# BT840_1_25mm_headers.net
KiCad netlist of a schematic drawn in EAGLE
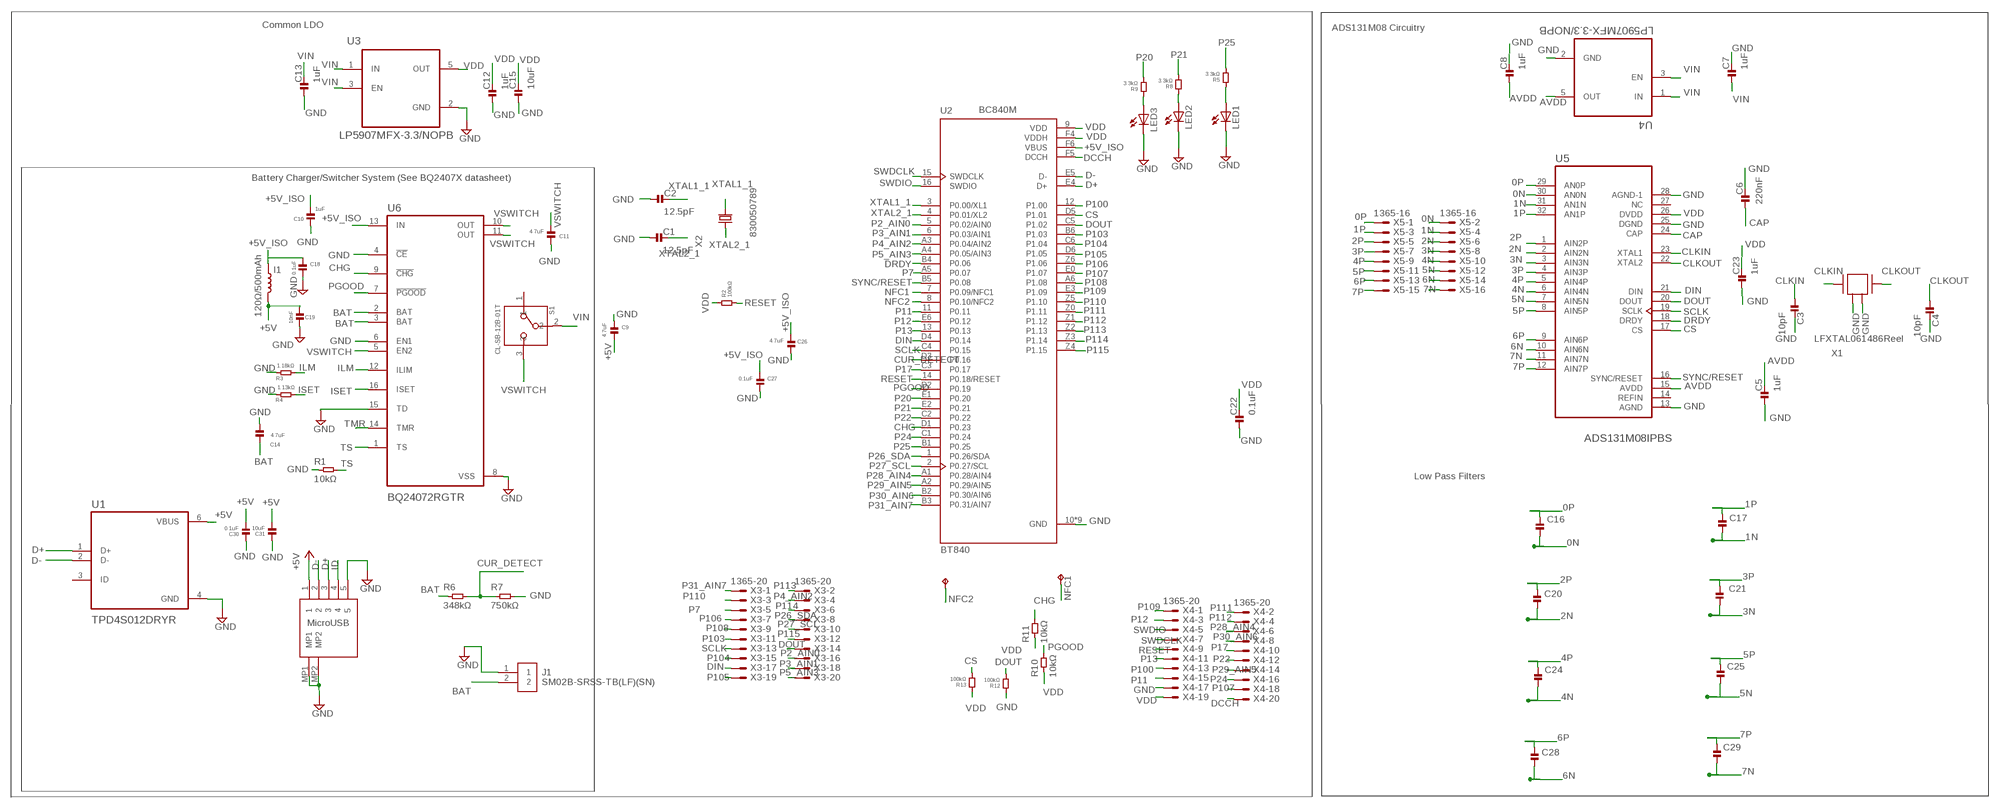
[diagram p0: schematic, sheet 1]

(export (version "E")
  (design (tool "Eeschema 10.0.6"))
  (components
    (comp (ref "C1")
      (value "12.5pF")
      (footprint "eagle-import:0201")
      (libsource (lib "eagle-import") (part "CAPACITOR.0201"))
    )
    (comp (ref "C2")
      (value "12.5pF")
      (footprint "eagle-import:0201")
      (libsource (lib "eagle-import") (part "CAPACITOR.0201"))
    )
    (comp (ref "C3")
      (value "10pF")
      (footprint "eagle-import:0201")
      (libsource (lib "eagle-import") (part "CAPACITOR.0201"))
    )
    (comp (ref "C4")
      (value "10pF")
      (footprint "eagle-import:0201")
      (libsource (lib "eagle-import") (part "CAPACITOR.0201"))
    )
    (comp (ref "C5")
      (value "1uF")
      (footprint "eagle-import:0201")
      (libsource (lib "eagle-import") (part "CAPACITOR.0201"))
    )
    (comp (ref "C6")
      (value "220nF")
      (footprint "eagle-import:0201")
      (libsource (lib "eagle-import") (part "CAPACITOR.0201"))
    )
    (comp (ref "C7")
      (value "1uF")
      (footprint "eagle-import:0201")
      (libsource (lib "eagle-import") (part "CAPACITOR.0201"))
    )
    (comp (ref "C8")
      (value "1uF")
      (footprint "eagle-import:0201")
      (libsource (lib "eagle-import") (part "CAPACITOR.0201"))
    )
    (comp (ref "C9")
      (value "4.7uF")
      (footprint "eagle-import:0201")
      (libsource (lib "eagle-import") (part "CAPACITOR.0201"))
    )
    (comp (ref "C10")
      (value "1uF")
      (footprint "eagle-import:0201")
      (libsource (lib "eagle-import") (part "CAPACITOR.0201"))
    )
    (comp (ref "C11")
      (value "4.7uF")
      (footprint "eagle-import:0201")
      (libsource (lib "eagle-import") (part "CAPACITOR.0201"))
    )
    (comp (ref "C12")
      (value "1uF")
      (footprint "eagle-import:0201")
      (libsource (lib "eagle-import") (part "CAPACITOR.0201"))
    )
    (comp (ref "C13")
      (value "1uF")
      (footprint "eagle-import:0201")
      (libsource (lib "eagle-import") (part "CAPACITOR.0201"))
    )
    (comp (ref "C14")
      (value "4.7uF")
      (footprint "eagle-import:0201")
      (libsource (lib "eagle-import") (part "CAPACITOR.0201"))
    )
    (comp (ref "C15")
      (value "10uF")
      (footprint "eagle-import:0402")
      (libsource (lib "eagle-import") (part "CAPACITOR.0402"))
    )
    (comp (ref "C16")
      (value "100pF")
      (footprint "eagle-import:0201")
      (libsource (lib "eagle-import") (part "CAPACITOR.0201"))
    )
    (comp (ref "C17")
      (value "100pF")
      (footprint "eagle-import:0201")
      (libsource (lib "eagle-import") (part "CAPACITOR.0201"))
    )
    (comp (ref "C18")
      (value "0.1uF")
      (footprint "eagle-import:0201")
      (libsource (lib "eagle-import") (part "CAPACITOR.0201"))
    )
    (comp (ref "C19")
      (value "10nF")
      (footprint "eagle-import:0201")
      (libsource (lib "eagle-import") (part "CAPACITOR.0201"))
    )
    (comp (ref "C20")
      (value "100pF")
      (footprint "eagle-import:0201")
      (libsource (lib "eagle-import") (part "CAPACITOR.0201"))
    )
    (comp (ref "C21")
      (value "100pF")
      (footprint "eagle-import:0201")
      (libsource (lib "eagle-import") (part "CAPACITOR.0201"))
    )
    (comp (ref "C22")
      (value "0.1uF")
      (footprint "eagle-import:0201")
      (libsource (lib "eagle-import") (part "CAPACITOR.0201"))
    )
    (comp (ref "C23")
      (value "1uF")
      (footprint "eagle-import:0201")
      (libsource (lib "eagle-import") (part "CAPACITOR.0201"))
    )
    (comp (ref "C24")
      (value "100pF")
      (footprint "eagle-import:0201")
      (libsource (lib "eagle-import") (part "CAPACITOR.0201"))
    )
    (comp (ref "C25")
      (value "100pF")
      (footprint "eagle-import:0201")
      (libsource (lib "eagle-import") (part "CAPACITOR.0201"))
    )
    (comp (ref "C26")
      (value "4.7uF")
      (footprint "eagle-import:0201")
      (libsource (lib "eagle-import") (part "CAPACITOR.0201"))
    )
    (comp (ref "C27")
      (value "0.1uF")
      (footprint "eagle-import:0201")
      (libsource (lib "eagle-import") (part "CAPACITOR.0201"))
    )
    (comp (ref "C28")
      (value "100pF")
      (footprint "eagle-import:0201")
      (libsource (lib "eagle-import") (part "CAPACITOR.0201"))
    )
    (comp (ref "C29")
      (value "100pF")
      (footprint "eagle-import:0201")
      (libsource (lib "eagle-import") (part "CAPACITOR.0201"))
    )
    (comp (ref "C30")
      (value "0.1uF")
      (footprint "eagle-import:0201")
      (libsource (lib "eagle-import") (part "CAPACITOR.0201"))
    )
    (comp (ref "C31")
      (value "10uF")
      (footprint "eagle-import:0402")
      (libsource (lib "eagle-import") (part "CAPACITOR.0402"))
    )
    (comp (ref "I1")
      (value "120Ω/500mAh")
      (footprint "eagle-import:0402_COILCRAFT")
      (fields (field (name "MOUSER_PART") "994-0402HP-12NXGLU"))
      (libsource (lib "eagle-import") (part "12NH-0402"))
    )
    (comp (ref "J1")
      (value "SM02B-SRSS-TB(LF)(SN)")
      (footprint "eagle-import:SM02B-SRSS-TB(LF)(SN)")
      (fields (field (name "MF") "JST Sales"))
      (libsource (lib "eagle-import") (part "SM02B-SRSS-TB(LF)(SN)"))
    )
    (comp (ref "LED1")
      (value "LEDCHIPLED_0603")
      (footprint "eagle-import:CHIPLED_0603")
      (libsource (lib "eagle-import") (part "LEDCHIPLED_0603"))
    )
    (comp (ref "LED2")
      (value "LEDCHIPLED_0603")
      (footprint "eagle-import:CHIPLED_0603")
      (libsource (lib "eagle-import") (part "LEDCHIPLED_0603"))
    )
    (comp (ref "LED3")
      (value "LEDCHIPLED_0603")
      (footprint "eagle-import:CHIPLED_0603")
      (libsource (lib "eagle-import") (part "LEDCHIPLED_0603"))
    )
    (comp (ref "NFC1")
      (value "TPTP14SQ")
      (footprint "eagle-import:TP14SQ")
      (libsource (lib "eagle-import") (part "TPTP14SQ"))
    )
    (comp (ref "NFC2")
      (value "TPTP14SQ")
      (footprint "eagle-import:TP14SQ")
      (libsource (lib "eagle-import") (part "TPTP14SQ"))
    )
    (comp (ref "R1")
      (value "10kΩ")
      (footprint "eagle-import:0201")
      (libsource (lib "eagle-import") (part "RESISTOR.0201"))
    )
    (comp (ref "R2")
      (value "100kΩ")
      (footprint "eagle-import:0201")
      (libsource (lib "eagle-import") (part "RESISTOR.0201"))
    )
    (comp (ref "R3")
      (value "1.18kΩ")
      (footprint "eagle-import:0201")
      (fields (field (name "SPICEPREFIX") "R"))
      (libsource (lib "eagle-import") (part "RESISTOR.0201"))
    )
    (comp (ref "R4")
      (value "1.13kΩ")
      (footprint "eagle-import:0201")
      (libsource (lib "eagle-import") (part "RESISTOR.0201"))
    )
    (comp (ref "R5")
      (value "3.3kΩ")
      (footprint "eagle-import:0201")
      (libsource (lib "eagle-import") (part "RESISTOR.0201"))
    )
    (comp (ref "R6")
      (value "348kΩ")
      (footprint "eagle-import:0201")
      (libsource (lib "eagle-import") (part "RESISTOR.0201"))
    )
    (comp (ref "R7")
      (value "750kΩ")
      (footprint "eagle-import:0201")
      (libsource (lib "eagle-import") (part "RESISTOR.0201"))
    )
    (comp (ref "R8")
      (value "3.3kΩ")
      (footprint "eagle-import:0201")
      (libsource (lib "eagle-import") (part "RESISTOR.0201"))
    )
    (comp (ref "R9")
      (value "3.3kΩ")
      (footprint "eagle-import:0201")
      (libsource (lib "eagle-import") (part "RESISTOR.0201"))
    )
    (comp (ref "R10")
      (value "10kΩ")
      (footprint "eagle-import:0402")
      (libsource (lib "eagle-import") (part "RESISTOR.0402"))
    )
    (comp (ref "R11")
      (value "10kΩ")
      (footprint "eagle-import:0402")
      (libsource (lib "eagle-import") (part "RESISTOR.0402"))
    )
    (comp (ref "R12")
      (value "100kΩ")
      (footprint "eagle-import:0402")
      (libsource (lib "eagle-import") (part "RESISTOR.0402"))
    )
    (comp (ref "R13")
      (value "100kΩ")
      (footprint "eagle-import:0402")
      (libsource (lib "eagle-import") (part "RESISTOR.0402"))
    )
    (comp (ref "S1")
      (value "CL-SB-12B-01T")
      (footprint "eagle-import:CL-SB-12B")
      (fields (field (name "MF") "Nidec Copal"))
      (libsource (lib "eagle-import") (part "CL-SB-12B-01T"))
    )
    (comp (ref "U1")
      (value "TPD4S012DRYR")
      (footprint "eagle-import:PSON50P145X100X60-6N")
      (fields (field (name "MF") "Texas Instruments"))
      (libsource (lib "eagle-import") (part "TPD4S012DRYR"))
    )
    (comp (ref "U2")
      (value "BT840")
      (footprint "eagle-import:XCVR_BT840")
      (fields (field (name "MF") "Fanstel Corp."))
      (libsource (lib "eagle-import") (part "BT840"))
    )
    (comp (ref "U3")
      (value "LP5907MFX-3.3/NOPB")
      (footprint "eagle-import:SOT95P280X145-5N")
      (fields (field (name "MF") "Texas Instruments"))
      (libsource (lib "eagle-import") (part "LP5907MFX-3.3/NOPB"))
    )
    (comp (ref "U4")
      (value "LP5907MFX-3.3/NOPB")
      (footprint "eagle-import:SOT95P280X145-5N")
      (fields (field (name "MF") "Texas Instruments"))
      (libsource (lib "eagle-import") (part "LP5907MFX-3.3/NOPB"))
    )
    (comp (ref "U5")
      (value "ADS131M08IPBS")
      (footprint "eagle-import:QFP50P700X700X120-32N")
      (fields (field (name "MF") "Texas Instruments"))
      (libsource (lib "eagle-import") (part "ADS131M08IPBS"))
    )
    (comp (ref "U6")
      (value "BQ24072RGTR")
      (footprint "eagle-import:QFN50P300X300X100-17N")
      (fields (field (name "MF") "Texas Instruments"))
      (libsource (lib "eagle-import") (part "BQ24072RGTR"))
    )
    (comp (ref "U7")
      (value "DX4R005JJ2R1800")
      (footprint "eagle-import:DX4R005JJ2R1800")
      (fields (field (name "MF") "JAE Electronics"))
      (libsource (lib "eagle-import") (part "DX4R005JJ2R1800"))
    )
    (comp (ref "X1")
      (value "ABM3B-8.000MHZ-B2-T")
      (footprint "eagle-import:ABM3B-8.000MHZ-B2-T")
      (fields
        (field (name "DIGIKEY_PART_NUMBER") "535-9720-2-ND")
        (field (name "MANUFACTURER") "Abracon LLC")
        (field (name "CREATED_BY") "PCBLayout.com")
      )
      (libsource (lib "eagle-import") (part "ABM3B-8.000MHZ-B2-T"))
    )
    (comp (ref "X2")
      (value "FC-12M")
      (footprint "eagle-import:FC-12M")
      (libsource (lib "eagle-import") (part "FC-12M"))
    )
    (comp (ref "X3")
      (value "1365-20")
      (footprint "eagle-import:1365-20")
      (libsource (lib "eagle-import") (part "1365-20"))
    )
    (comp (ref "X4")
      (value "1365-20")
      (footprint "eagle-import:1365-20")
      (libsource (lib "eagle-import") (part "1365-20"))
    )
    (comp (ref "X5")
      (value "1365-16")
      (footprint "eagle-import:1365-16")
      (libsource (lib "eagle-import") (part "1365-16"))
    )
  )
  (nets
    (net (code "1") (name "+5V") (class "Default")
      (node (ref "C19") (pin "2") (pinfunction "2_2") (pintype "bidirectional"))
      (node (ref "C30") (pin "2") (pinfunction "2_2") (pintype "bidirectional"))
      (node (ref "C31") (pin "2") (pinfunction "2_2") (pintype "bidirectional"))
      (node (ref "C9") (pin "2") (pinfunction "2_2") (pintype "bidirectional"))
      (node (ref "I1") (pin "P$2") (pinfunction "2_P$2") (pintype "passive"))
      (node (ref "U1") (pin "6") (pinfunction "VBUS_6") (pintype "power_in"))
      (node (ref "U7") (pin "1") (pinfunction "1_1") (pintype "bidirectional"))
    )
    (net (code "2") (name "+5V_ISO") (class "Default")
      (node (ref "C10") (pin "2") (pinfunction "2_2") (pintype "bidirectional"))
      (node (ref "C18") (pin "1") (pinfunction "1_1") (pintype "bidirectional"))
      (node (ref "C26") (pin "2") (pinfunction "2_2") (pintype "bidirectional"))
      (node (ref "C27") (pin "2") (pinfunction "2_2") (pintype "bidirectional"))
      (node (ref "I1") (pin "P$1") (pinfunction "1_P$1") (pintype "passive"))
      (node (ref "U2") (pin "F6") (pinfunction "VBUS_F6") (pintype "power_in"))
      (node (ref "U6") (pin "13") (pinfunction "IN_13") (pintype "input"))
    )
    (net (code "3") (name "0N") (class "Default")
      (node (ref "C16") (pin "2") (pinfunction "2_2") (pintype "bidirectional"))
      (node (ref "U5") (pin "30") (pinfunction "AN0N_30") (pintype "bidirectional"))
      (node (ref "X5") (pin "2") (pinfunction "S_2") (pintype "passive"))
    )
    (net (code "4") (name "0P") (class "Default")
      (node (ref "C16") (pin "1") (pinfunction "1_1") (pintype "bidirectional"))
      (node (ref "U5") (pin "29") (pinfunction "AN0P_29") (pintype "bidirectional"))
      (node (ref "X5") (pin "1") (pinfunction "S_1") (pintype "passive"))
    )
    (net (code "5") (name "1N") (class "Default")
      (node (ref "C17") (pin "2") (pinfunction "2_2") (pintype "bidirectional"))
      (node (ref "U5") (pin "31") (pinfunction "AN1N_31") (pintype "bidirectional"))
      (node (ref "X5") (pin "4") (pinfunction "S_4") (pintype "passive"))
    )
    (net (code "6") (name "1P") (class "Default")
      (node (ref "C17") (pin "1") (pinfunction "1_1") (pintype "bidirectional"))
      (node (ref "U5") (pin "32") (pinfunction "AN1P_32") (pintype "bidirectional"))
      (node (ref "X5") (pin "3") (pinfunction "S_3") (pintype "passive"))
    )
    (net (code "7") (name "2N") (class "Default")
      (node (ref "C20") (pin "2") (pinfunction "2_2") (pintype "bidirectional"))
      (node (ref "U5") (pin "2") (pinfunction "AIN2N_2") (pintype "input"))
      (node (ref "X5") (pin "6") (pinfunction "S_6") (pintype "passive"))
    )
    (net (code "8") (name "2P") (class "Default")
      (node (ref "C20") (pin "1") (pinfunction "1_1") (pintype "bidirectional"))
      (node (ref "U5") (pin "1") (pinfunction "AIN2P_1") (pintype "input"))
      (node (ref "X5") (pin "5") (pinfunction "S_5") (pintype "passive"))
    )
    (net (code "9") (name "3N") (class "Default")
      (node (ref "C21") (pin "2") (pinfunction "2_2") (pintype "bidirectional"))
      (node (ref "U5") (pin "3") (pinfunction "AIN3N_3") (pintype "input"))
      (node (ref "X5") (pin "8") (pinfunction "S_8") (pintype "passive"))
    )
    (net (code "10") (name "3P") (class "Default")
      (node (ref "C21") (pin "1") (pinfunction "1_1") (pintype "bidirectional"))
      (node (ref "U5") (pin "4") (pinfunction "AIN3P_4") (pintype "input"))
      (node (ref "X5") (pin "7") (pinfunction "S_7") (pintype "passive"))
    )
    (net (code "11") (name "4N") (class "Default")
      (node (ref "C24") (pin "2") (pinfunction "2_2") (pintype "bidirectional"))
      (node (ref "U5") (pin "6") (pinfunction "AIN4N_6") (pintype "input"))
      (node (ref "X5") (pin "10") (pinfunction "S_10") (pintype "passive"))
    )
    (net (code "12") (name "4P") (class "Default")
      (node (ref "C24") (pin "1") (pinfunction "1_1") (pintype "bidirectional"))
      (node (ref "U5") (pin "5") (pinfunction "AIN4P_5") (pintype "input"))
      (node (ref "X5") (pin "9") (pinfunction "S_9") (pintype "passive"))
    )
    (net (code "13") (name "5N") (class "Default")
      (node (ref "C25") (pin "2") (pinfunction "2_2") (pintype "bidirectional"))
      (node (ref "U5") (pin "7") (pinfunction "AIN5N_7") (pintype "input"))
      (node (ref "X5") (pin "12") (pinfunction "S_12") (pintype "passive"))
    )
    (net (code "14") (name "5P") (class "Default")
      (node (ref "C25") (pin "1") (pinfunction "1_1") (pintype "bidirectional"))
      (node (ref "U5") (pin "8") (pinfunction "AIN5P_8") (pintype "input"))
      (node (ref "X5") (pin "11") (pinfunction "S_11") (pintype "passive"))
    )
    (net (code "15") (name "6N") (class "Default")
      (node (ref "C28") (pin "2") (pinfunction "2_2") (pintype "bidirectional"))
      (node (ref "U5") (pin "10") (pinfunction "AIN6N_10") (pintype "input"))
      (node (ref "X5") (pin "14") (pinfunction "S_14") (pintype "passive"))
    )
    (net (code "16") (name "6P") (class "Default")
      (node (ref "C28") (pin "1") (pinfunction "1_1") (pintype "bidirectional"))
      (node (ref "U5") (pin "9") (pinfunction "AIN6P_9") (pintype "input"))
      (node (ref "X5") (pin "13") (pinfunction "S_13") (pintype "passive"))
    )
    (net (code "17") (name "7N") (class "Default")
      (node (ref "C29") (pin "2") (pinfunction "2_2") (pintype "bidirectional"))
      (node (ref "U5") (pin "11") (pinfunction "AIN7N_11") (pintype "input"))
      (node (ref "X5") (pin "16") (pinfunction "S_16") (pintype "passive"))
    )
    (net (code "18") (name "7P") (class "Default")
      (node (ref "C29") (pin "1") (pinfunction "1_1") (pintype "bidirectional"))
      (node (ref "U5") (pin "12") (pinfunction "AIN7P_12") (pintype "input"))
      (node (ref "X5") (pin "15") (pinfunction "S_15") (pintype "passive"))
    )
    (net (code "19") (name "AVDD") (class "Default")
      (node (ref "C5") (pin "2") (pinfunction "2_2") (pintype "bidirectional"))
      (node (ref "C8") (pin "1") (pinfunction "1_1") (pintype "bidirectional"))
      (node (ref "U4") (pin "5") (pinfunction "OUT_5") (pintype "output"))
      (node (ref "U5") (pin "15") (pinfunction "AVDD_15") (pintype "power_in"))
    )
    (net (code "20") (name "BAT") (class "Default")
      (node (ref "C14") (pin "2") (pinfunction "2_2") (pintype "bidirectional"))
      (node (ref "J1") (pin "2") (pinfunction "2_2") (pintype "bidirectional"))
      (node (ref "R6") (pin "1") (pinfunction "1_1") (pintype "bidirectional"))
      (node (ref "U6") (pin "2") (pinfunction "BAT_2") (pintype "bidirectional"))
      (node (ref "U6") (pin "3") (pinfunction "BAT_3") (pintype "bidirectional"))
    )
    (net (code "21") (name "CAP") (class "Default")
      (node (ref "C6") (pin "1") (pinfunction "1_1") (pintype "bidirectional"))
      (node (ref "U5") (pin "24") (pinfunction "CAP_24") (pintype "bidirectional"))
    )
    (net (code "22") (name "CHG") (class "Default")
      (node (ref "R11") (pin "2") (pinfunction "2_2") (pintype "bidirectional"))
      (node (ref "U2") (pin "D1") (pinfunction "P0.23_D1") (pintype "bidirectional"))
      (node (ref "U6") (pin "9") (pinfunction "~{CHG}_9") (pintype "bidirectional"))
    )
    (net (code "23") (name "CLKIN") (class "Default")
      (node (ref "C3") (pin "1") (pinfunction "1_1") (pintype "bidirectional"))
      (node (ref "U5") (pin "23") (pinfunction "XTAL1_23") (pintype "bidirectional"))
      (node (ref "X1") (pin "1") (pinfunction "1_1") (pintype "passive"))
    )
    (net (code "24") (name "CLKOUT") (class "Default")
      (node (ref "C4") (pin "1") (pinfunction "1_1") (pintype "bidirectional"))
      (node (ref "U5") (pin "22") (pinfunction "XTAL2_22") (pintype "bidirectional"))
      (node (ref "X1") (pin "3") (pinfunction "3_3") (pintype "passive"))
    )
    (net (code "25") (name "CS") (class "Default")
      (node (ref "R13") (pin "1") (pinfunction "1_1") (pintype "bidirectional"))
      (node (ref "U2") (pin "D5") (pinfunction "P1.01_D5") (pintype "bidirectional"))
      (node (ref "U5") (pin "17") (pinfunction "CS_17") (pintype "bidirectional"))
    )
    (net (code "26") (name "CUR_DETECT") (class "Default")
      (node (ref "R6") (pin "2") (pinfunction "2_2") (pintype "bidirectional"))
      (node (ref "R7") (pin "1") (pinfunction "1_1") (pintype "bidirectional"))
      (node (ref "U2") (pin "D3") (pinfunction "P0.16_D3") (pintype "bidirectional"))
    )
    (net (code "27") (name "D+") (class "Default")
      (node (ref "U1") (pin "1") (pinfunction "D+_1") (pintype "bidirectional"))
      (node (ref "U2") (pin "E4") (pinfunction "D+_E4") (pintype "bidirectional"))
      (node (ref "U7") (pin "3") (pinfunction "3_3") (pintype "bidirectional"))
    )
    (net (code "28") (name "D-") (class "Default")
      (node (ref "U1") (pin "2") (pinfunction "D-_2") (pintype "bidirectional"))
      (node (ref "U2") (pin "E5") (pinfunction "D-_E5") (pintype "bidirectional"))
      (node (ref "U7") (pin "2") (pinfunction "2_2") (pintype "bidirectional"))
    )
    (net (code "29") (name "DCCH") (class "Default")
      (node (ref "U2") (pin "F5") (pinfunction "DCCH_F5") (pintype "power_in"))
      (node (ref "X4") (pin "20") (pinfunction "S_20") (pintype "passive"))
    )
    (net (code "30") (name "DIN") (class "Default")
      (node (ref "U2") (pin "D4") (pinfunction "P0.14_D4") (pintype "bidirectional"))
      (node (ref "U5") (pin "21") (pinfunction "DIN_21") (pintype "input"))
      (node (ref "X3") (pin "17") (pinfunction "S_17") (pintype "passive"))
    )
    (net (code "31") (name "DOUT") (class "Default")
      (node (ref "R12") (pin "1") (pinfunction "1_1") (pintype "bidirectional"))
      (node (ref "U2") (pin "C5") (pinfunction "P1.02_C5") (pintype "bidirectional"))
      (node (ref "U5") (pin "20") (pinfunction "DOUT_20") (pintype "output"))
      (node (ref "X3") (pin "14") (pinfunction "S_14") (pintype "passive"))
    )
    (net (code "32") (name "DRDY") (class "Default")
      (node (ref "U2") (pin "B4") (pinfunction "P0.06_B4") (pintype "bidirectional"))
      (node (ref "U5") (pin "18") (pinfunction "DRDY_18") (pintype "output"))
    )
    (net (code "33") (name "GND") (class "Default")
      (node (ref "C1") (pin "1") (pinfunction "1_1") (pintype "bidirectional"))
      (node (ref "C10") (pin "1") (pinfunction "1_1") (pintype "bidirectional"))
      (node (ref "C11") (pin "1") (pinfunction "1_1") (pintype "bidirectional"))
      (node (ref "C12") (pin "1") (pinfunction "1_1") (pintype "bidirectional"))
      (node (ref "C13") (pin "1") (pinfunction "1_1") (pintype "bidirectional"))
      (node (ref "C14") (pin "1") (pinfunction "1_1") (pintype "bidirectional"))
      (node (ref "C15") (pin "1") (pinfunction "1_1") (pintype "bidirectional"))
      (node (ref "C18") (pin "2") (pinfunction "2_2") (pintype "bidirectional"))
      (node (ref "C19") (pin "1") (pinfunction "1_1") (pintype "bidirectional"))
      (node (ref "C2") (pin "1") (pinfunction "1_1") (pintype "bidirectional"))
      (node (ref "C22") (pin "1") (pinfunction "1_1") (pintype "bidirectional"))
      (node (ref "C23") (pin "1") (pinfunction "1_1") (pintype "bidirectional"))
      (node (ref "C26") (pin "1") (pinfunction "1_1") (pintype "bidirectional"))
      (node (ref "C27") (pin "1") (pinfunction "1_1") (pintype "bidirectional"))
      (node (ref "C3") (pin "2") (pinfunction "2_2") (pintype "bidirectional"))
      (node (ref "C30") (pin "1") (pinfunction "1_1") (pintype "bidirectional"))
      (node (ref "C31") (pin "1") (pinfunction "1_1") (pintype "bidirectional"))
      (node (ref "C4") (pin "2") (pinfunction "2_2") (pintype "bidirectional"))
      (node (ref "C5") (pin "1") (pinfunction "1_1") (pintype "bidirectional"))
      (node (ref "C6") (pin "2") (pinfunction "2_2") (pintype "bidirectional"))
      (node (ref "C7") (pin "2") (pinfunction "2_2") (pintype "bidirectional"))
      (node (ref "C8") (pin "2") (pinfunction "2_2") (pintype "bidirectional"))
      (node (ref "C9") (pin "1") (pinfunction "1_1") (pintype "bidirectional"))
      (node (ref "J1") (pin "1") (pinfunction "1_1") (pintype "bidirectional"))
      (node (ref "LED1") (pin "C") (pinfunction "C_C") (pintype "passive"))
      (node (ref "LED2") (pin "C") (pinfunction "C_C") (pintype "passive"))
      (node (ref "LED3") (pin "C") (pinfunction "C_C") (pintype "passive"))
      (node (ref "R1") (pin "1") (pinfunction "1_1") (pintype "bidirectional"))
      (node (ref "R12") (pin "2") (pinfunction "2_2") (pintype "bidirectional"))
      (node (ref "R3") (pin "1") (pinfunction "1_1") (pintype "bidirectional"))
      (node (ref "R4") (pin "1") (pinfunction "1_1") (pintype "bidirectional"))
      (node (ref "R7") (pin "2") (pinfunction "2_2") (pintype "bidirectional"))
      (node (ref "U1") (pin "4") (pinfunction "GND_4") (pintype "power_in"))
      (node (ref "U2") (pin "10") (pinfunction "GND_10") (pintype "power_in"))
      (node (ref "U2") (pin "A0") (pinfunction "GND_A0") (pintype "power_in"))
      (node (ref "U2") (pin "B0") (pinfunction "GND_B0") (pintype "power_in"))
      (node (ref "U2") (pin "C0") (pinfunction "GND_C0") (pintype "power_in"))
      (node (ref "U2") (pin "D0") (pinfunction "GND_D0") (pintype "power_in"))
      (node (ref "U2") (pin "F0") (pinfunction "GND_F0") (pintype "power_in"))
      (node (ref "U2") (pin "F1") (pinfunction "GND_F1") (pintype "power_in"))
      (node (ref "U2") (pin "F2") (pinfunction "GND_F2") (pintype "power_in"))
      (node (ref "U2") (pin "F3") (pinfunction "GND_F3") (pintype "power_in"))
      (node (ref "U3") (pin "2") (pinfunction "GND_2") (pintype "power_in"))
      (node (ref "U4") (pin "2") (pinfunction "GND_2") (pintype "power_in"))
      (node (ref "U5") (pin "13") (pinfunction "AGND_13") (pintype "power_in"))
      (node (ref "U5") (pin "25") (pinfunction "DGND_25") (pintype "power_in"))
      (node (ref "U5") (pin "28") (pinfunction "AGND-1_28") (pintype "power_in"))
      (node (ref "U6") (pin "15") (pinfunction "TD_15") (pintype "bidirectional"))
      (node (ref "U6") (pin "4") (pinfunction "~{CE}_4") (pintype "bidirectional"))
      (node (ref "U6") (pin "6") (pinfunction "EN1_6") (pintype "bidirectional"))
      (node (ref "U6") (pin "8") (pinfunction "VSS_8") (pintype "power_in"))
      (node (ref "U7") (pin "5") (pinfunction "5_5") (pintype "bidirectional"))
      (node (ref "U7") (pin "MP1") (pinfunction "MP1_MP1") (pintype "bidirectional"))
      (node (ref "U7") (pin "MP2") (pinfunction "MP2_MP2") (pintype "bidirectional"))
      (node (ref "X1") (pin "2") (pinfunction "2_2") (pintype "passive"))
      (node (ref "X1") (pin "4") (pinfunction "4_4") (pintype "passive"))
      (node (ref "X4") (pin "17") (pinfunction "S_17") (pintype "passive"))
    )
    (net (code "34") (name "ID") (class "Default")
      (node (ref "U7") (pin "4") (pinfunction "4_4") (pintype "bidirectional"))
    )
    (net (code "35") (name "ILM") (class "Default")
      (node (ref "R3") (pin "2") (pinfunction "2_2") (pintype "bidirectional"))
      (node (ref "U6") (pin "12") (pinfunction "ILIM_12") (pintype "bidirectional"))
    )
    (net (code "36") (name "ISET") (class "Default")
      (node (ref "R4") (pin "2") (pinfunction "2_2") (pintype "bidirectional"))
      (node (ref "U6") (pin "16") (pinfunction "ISET_16") (pintype "bidirectional"))
    )
    (net (code "37") (name "NFC1") (class "Default")
      (node (ref "NFC2") (pin "TP") (pinfunction "TP_TP") (pintype "input"))
      (node (ref "U2") (pin "7") (pinfunction "P0.09/NFC1_7") (pintype "bidirectional"))
    )
    (net (code "38") (name "NFC2") (class "Default")
      (node (ref "NFC1") (pin "TP") (pinfunction "TP_TP") (pintype "input"))
      (node (ref "U2") (pin "8") (pinfunction "P0.10/NFC2_8") (pintype "bidirectional"))
    )
    (net (code "39") (name "Net-(LED1-PadA)") (class "Default")
      (node (ref "LED1") (pin "A") (pinfunction "A_A") (pintype "passive"))
      (node (ref "R5") (pin "2") (pinfunction "2_2") (pintype "bidirectional"))
    )
    (net (code "40") (name "Net-(LED2-PadA)") (class "Default")
      (node (ref "LED2") (pin "A") (pinfunction "A_A") (pintype "passive"))
      (node (ref "R8") (pin "2") (pinfunction "2_2") (pintype "bidirectional"))
    )
    (net (code "41") (name "Net-(LED3-PadA)") (class "Default")
      (node (ref "LED3") (pin "A") (pinfunction "A_A") (pintype "passive"))
      (node (ref "R9") (pin "2") (pinfunction "2_2") (pintype "bidirectional"))
    )
    (net (code "42") (name "P2_AIN0") (class "Default")
      (node (ref "U2") (pin "5") (pinfunction "P0.02/AIN0_5") (pintype "bidirectional"))
      (node (ref "X3") (pin "16") (pinfunction "S_16") (pintype "passive"))
    )
    (net (code "43") (name "P3_AIN1") (class "Default")
      (node (ref "U2") (pin "6") (pinfunction "P0.03/AIN1_6") (pintype "bidirectional"))
      (node (ref "X3") (pin "18") (pinfunction "S_18") (pintype "passive"))
    )
    (net (code "44") (name "P4_AIN2") (class "Default")
      (node (ref "U2") (pin "A3") (pinfunction "P0.04/AIN2_A3") (pintype "bidirectional"))
      (node (ref "X3") (pin "4") (pinfunction "S_4") (pintype "passive"))
    )
    (net (code "45") (name "P5_AIN3") (class "Default")
      (node (ref "U2") (pin "A4") (pinfunction "P0.05/AIN3_A4") (pintype "bidirectional"))
      (node (ref "X3") (pin "20") (pinfunction "S_20") (pintype "passive"))
    )
    (net (code "46") (name "P7") (class "Default")
      (node (ref "U2") (pin "A5") (pinfunction "P0.07_A5") (pintype "bidirectional"))
      (node (ref "X3") (pin "5") (pinfunction "S_5") (pintype "passive"))
    )
    (net (code "47") (name "P11") (class "Default")
      (node (ref "U2") (pin "11") (pinfunction "P0.11_11") (pintype "bidirectional"))
      (node (ref "X4") (pin "15") (pinfunction "S_15") (pintype "passive"))
    )
    (net (code "48") (name "P12") (class "Default")
      (node (ref "U2") (pin "E6") (pinfunction "P0.12_E6") (pintype "bidirectional"))
      (node (ref "X4") (pin "3") (pinfunction "S_3") (pintype "passive"))
    )
    (net (code "49") (name "P13") (class "Default")
      (node (ref "U2") (pin "13") (pinfunction "P0.13_13") (pintype "bidirectional"))
      (node (ref "X4") (pin "11") (pinfunction "S_11") (pintype "passive"))
    )
    (net (code "50") (name "P17") (class "Default")
      (node (ref "U2") (pin "C3") (pinfunction "P0.17_C3") (pintype "bidirectional"))
      (node (ref "X4") (pin "10") (pinfunction "S_10") (pintype "passive"))
    )
    (net (code "51") (name "P20") (class "Default")
      (node (ref "R9") (pin "1") (pinfunction "1_1") (pintype "bidirectional"))
      (node (ref "U2") (pin "E1") (pinfunction "P0.20_E1") (pintype "bidirectional"))
    )
    (net (code "52") (name "P21") (class "Default")
      (node (ref "R8") (pin "1") (pinfunction "1_1") (pintype "bidirectional"))
      (node (ref "U2") (pin "E2") (pinfunction "P0.21_E2") (pintype "bidirectional"))
    )
    (net (code "53") (name "P22") (class "Default")
      (node (ref "U2") (pin "C2") (pinfunction "P0.22_C2") (pintype "bidirectional"))
      (node (ref "X4") (pin "12") (pinfunction "S_12") (pintype "passive"))
    )
    (net (code "54") (name "P24") (class "Default")
      (node (ref "U2") (pin "C1") (pinfunction "P0.24_C1") (pintype "bidirectional"))
      (node (ref "X4") (pin "16") (pinfunction "S_16") (pintype "passive"))
    )
    (net (code "55") (name "P25") (class "Default")
      (node (ref "R5") (pin "1") (pinfunction "1_1") (pintype "bidirectional"))
      (node (ref "U2") (pin "B1") (pinfunction "P0.25_B1") (pintype "bidirectional"))
    )
    (net (code "56") (name "P26_SDA") (class "Default")
      (node (ref "U2") (pin "1") (pinfunction "P0.26/SDA_1") (pintype "bidirectional"))
      (node (ref "X3") (pin "8") (pinfunction "S_8") (pintype "passive"))
    )
    (net (code "57") (name "P27_SCL") (class "Default")
      (node (ref "U2") (pin "2") (pinfunction "P0.27/SCL_2") (pintype "bidirectional"))
      (node (ref "X3") (pin "10") (pinfunction "S_10") (pintype "passive"))
    )
    (net (code "58") (name "P28_AIN4") (class "Default")
      (node (ref "U2") (pin "A1") (pinfunction "P0.28/AIN4_A1") (pintype "bidirectional"))
      (node (ref "X4") (pin "6") (pinfunction "S_6") (pintype "passive"))
    )
    (net (code "59") (name "P29_AIN5") (class "Default")
      (node (ref "U2") (pin "A2") (pinfunction "P0.29/AIN5_A2") (pintype "bidirectional"))
      (node (ref "X4") (pin "14") (pinfunction "S_14") (pintype "passive"))
    )
    (net (code "60") (name "P30_AIN6") (class "Default")
      (node (ref "U2") (pin "B2") (pinfunction "P0.30/AIN6_B2") (pintype "bidirectional"))
      (node (ref "X4") (pin "8") (pinfunction "S_8") (pintype "passive"))
    )
    (net (code "61") (name "P31_AIN7") (class "Default")
      (node (ref "U2") (pin "B3") (pinfunction "P0.31/AIN7_B3") (pintype "bidirectional"))
      (node (ref "X3") (pin "1") (pinfunction "S_1") (pintype "passive"))
    )
    (net (code "62") (name "P100") (class "Default")
      (node (ref "U2") (pin "12") (pinfunction "P1.00_12") (pintype "bidirectional"))
      (node (ref "X4") (pin "13") (pinfunction "S_13") (pintype "passive"))
    )
    (net (code "63") (name "P103") (class "Default")
      (node (ref "U2") (pin "B6") (pinfunction "P1.03_B6") (pintype "bidirectional"))
      (node (ref "X3") (pin "11") (pinfunction "S_11") (pintype "passive"))
    )
    (net (code "64") (name "P104") (class "Default")
      (node (ref "U2") (pin "C6") (pinfunction "P1.04_C6") (pintype "bidirectional"))
      (node (ref "X3") (pin "15") (pinfunction "S_15") (pintype "passive"))
    )
    (net (code "65") (name "P105") (class "Default")
      (node (ref "U2") (pin "D6") (pinfunction "P1.05_D6") (pintype "bidirectional"))
      (node (ref "X3") (pin "19") (pinfunction "S_19") (pintype "passive"))
    )
    (net (code "66") (name "P106") (class "Default")
      (node (ref "U2") (pin "Z6") (pinfunction "P1.06_Z6") (pintype "bidirectional"))
      (node (ref "X3") (pin "7") (pinfunction "S_7") (pintype "passive"))
    )
    (net (code "67") (name "P107") (class "Default")
      (node (ref "U2") (pin "E0") (pinfunction "P1.07_E0") (pintype "bidirectional"))
      (node (ref "X4") (pin "18") (pinfunction "S_18") (pintype "passive"))
    )
    (net (code "68") (name "P108") (class "Default")
      (node (ref "U2") (pin "A6") (pinfunction "P1.08_A6") (pintype "bidirectional"))
      (node (ref "X3") (pin "9") (pinfunction "S_9") (pintype "passive"))
    )
    (net (code "69") (name "P109") (class "Default")
      (node (ref "U2") (pin "E3") (pinfunction "P1.09_E3") (pintype "bidirectional"))
      (node (ref "X4") (pin "1") (pinfunction "S_1") (pintype "passive"))
    )
    (net (code "70") (name "P110") (class "Default")
      (node (ref "U2") (pin "Z5") (pinfunction "P1.10_Z5") (pintype "bidirectional"))
      (node (ref "X3") (pin "3") (pinfunction "S_3") (pintype "passive"))
    )
    (net (code "71") (name "P111") (class "Default")
      (node (ref "U2") (pin "Z0") (pinfunction "P1.11_Z0") (pintype "bidirectional"))
      (node (ref "X4") (pin "2") (pinfunction "S_2") (pintype "passive"))
    )
    (net (code "72") (name "P112") (class "Default")
      (node (ref "U2") (pin "Z1") (pinfunction "P1.12_Z1") (pintype "bidirectional"))
      (node (ref "X4") (pin "4") (pinfunction "S_4") (pintype "passive"))
    )
    (net (code "73") (name "P113") (class "Default")
      (node (ref "U2") (pin "Z2") (pinfunction "P1.13_Z2") (pintype "bidirectional"))
      (node (ref "X3") (pin "2") (pinfunction "S_2") (pintype "passive"))
    )
    (net (code "74") (name "P114") (class "Default")
      (node (ref "U2") (pin "Z3") (pinfunction "P1.14_Z3") (pintype "bidirectional"))
      (node (ref "X3") (pin "6") (pinfunction "S_6") (pintype "passive"))
    )
    (net (code "75") (name "P115") (class "Default")
      (node (ref "U2") (pin "Z4") (pinfunction "P1.15_Z4") (pintype "bidirectional"))
      (node (ref "X3") (pin "12") (pinfunction "S_12") (pintype "passive"))
    )
    (net (code "76") (name "PGOOD") (class "Default")
      (node (ref "R10") (pin "2") (pinfunction "2_2") (pintype "bidirectional"))
      (node (ref "U2") (pin "D2") (pinfunction "P0.19_D2") (pintype "bidirectional"))
      (node (ref "U6") (pin "7") (pinfunction "~{PGOOD}_7") (pintype "bidirectional"))
    )
    (net (code "77") (name "RESET") (class "Default")
      (node (ref "R2") (pin "1") (pinfunction "1_1") (pintype "bidirectional"))
      (node (ref "U2") (pin "14") (pinfunction "P0.18/RESET_14") (pintype "bidirectional"))
      (node (ref "X4") (pin "9") (pinfunction "S_9") (pintype "passive"))
    )
    (net (code "78") (name "SCLK") (class "Default")
      (node (ref "U2") (pin "C4") (pinfunction "P0.15_C4") (pintype "bidirectional"))
      (node (ref "U5") (pin "19") (pinfunction "SCLK_19") (pintype "input"))
      (node (ref "X3") (pin "13") (pinfunction "S_13") (pintype "passive"))
    )
    (net (code "79") (name "SWDCLK") (class "Default")
      (node (ref "U2") (pin "15") (pinfunction "SWDCLK_15") (pintype "input"))
      (node (ref "X4") (pin "7") (pinfunction "S_7") (pintype "passive"))
    )
    (net (code "80") (name "SWDIO") (class "Default")
      (node (ref "U2") (pin "16") (pinfunction "SWDIO_16") (pintype "bidirectional"))
      (node (ref "X4") (pin "5") (pinfunction "S_5") (pintype "passive"))
    )
    (net (code "81") (name "SYNC{slash}RESET") (class "Default")
      (node (ref "U2") (pin "B5") (pinfunction "P0.08_B5") (pintype "bidirectional"))
      (node (ref "U5") (pin "16") (pinfunction "SYNC/RESET_16") (pintype "bidirectional"))
    )
    (net (code "82") (name "TMR") (class "Default")
      (node (ref "U6") (pin "14") (pinfunction "TMR_14") (pintype "bidirectional"))
    )
    (net (code "83") (name "TS") (class "Default")
      (node (ref "R1") (pin "2") (pinfunction "2_2") (pintype "bidirectional"))
      (node (ref "U6") (pin "1") (pinfunction "TS_1") (pintype "bidirectional"))
    )
    (net (code "84") (name "VDD") (class "Default")
      (node (ref "C12") (pin "2") (pinfunction "2_2") (pintype "bidirectional"))
      (node (ref "C15") (pin "2") (pinfunction "2_2") (pintype "bidirectional"))
      (node (ref "C22") (pin "2") (pinfunction "2_2") (pintype "bidirectional"))
      (node (ref "C23") (pin "2") (pinfunction "2_2") (pintype "bidirectional"))
      (node (ref "R10") (pin "1") (pinfunction "1_1") (pintype "bidirectional"))
      (node (ref "R11") (pin "1") (pinfunction "1_1") (pintype "bidirectional"))
      (node (ref "R13") (pin "2") (pinfunction "2_2") (pintype "bidirectional"))
      (node (ref "R2") (pin "2") (pinfunction "2_2") (pintype "bidirectional"))
      (node (ref "U2") (pin "9") (pinfunction "VDD_9") (pintype "power_in"))
      (node (ref "U2") (pin "F4") (pinfunction "VDDH_F4") (pintype "power_in"))
      (node (ref "U3") (pin "5") (pinfunction "OUT_5") (pintype "output"))
      (node (ref "U5") (pin "26") (pinfunction "DVDD_26") (pintype "power_in"))
      (node (ref "X4") (pin "19") (pinfunction "S_19") (pintype "passive"))
    )
    (net (code "85") (name "VIN") (class "Default")
      (node (ref "C13") (pin "2") (pinfunction "2_2") (pintype "bidirectional"))
      (node (ref "C7") (pin "1") (pinfunction "1_1") (pintype "bidirectional"))
      (node (ref "S1") (pin "2") (pinfunction "2_2") (pintype "bidirectional"))
      (node (ref "U3") (pin "1") (pinfunction "IN_1") (pintype "input"))
      (node (ref "U3") (pin "3") (pinfunction "EN_3") (pintype "input"))
      (node (ref "U4") (pin "1") (pinfunction "IN_1") (pintype "input"))
      (node (ref "U4") (pin "3") (pinfunction "EN_3") (pintype "input"))
    )
    (net (code "86") (name "VSWITCH") (class "Default")
      (node (ref "C11") (pin "2") (pinfunction "2_2") (pintype "bidirectional"))
      (node (ref "S1") (pin "3") (pinfunction "3_3") (pintype "bidirectional"))
      (node (ref "U6") (pin "10") (pinfunction "OUT_10") (pintype "output"))
      (node (ref "U6") (pin "11") (pinfunction "OUT_11") (pintype "output"))
      (node (ref "U6") (pin "5") (pinfunction "EN2_5") (pintype "bidirectional"))
    )
    (net (code "87") (name "XTAL1_1") (class "Default")
      (node (ref "C2") (pin "2") (pinfunction "2_2") (pintype "bidirectional"))
      (node (ref "U2") (pin "3") (pinfunction "P0.00/XL1_3") (pintype "bidirectional"))
      (node (ref "X2") (pin "2") (pinfunction "2_2") (pintype "passive"))
    )
    (net (code "88") (name "XTAL2_1") (class "Default")
      (node (ref "C1") (pin "2") (pinfunction "2_2") (pintype "bidirectional"))
      (node (ref "U2") (pin "4") (pinfunction "P0.01/XL2_4") (pintype "bidirectional"))
      (node (ref "X2") (pin "1") (pinfunction "1_1") (pintype "passive"))
    )
    (net (code "89") (name "unconnected-(S1-Pad1)") (class "Default")
      (node (ref "S1") (pin "1") (pinfunction "1_1") (pintype "bidirectional"))
    )
    (net (code "90") (name "unconnected-(U1-ID-Pad3)") (class "Default")
      (node (ref "U1") (pin "3") (pinfunction "ID_3") (pintype "bidirectional"))
    )
    (net (code "91") (name "unconnected-(U5-NC-Pad27)") (class "Default")
      (node (ref "U5") (pin "27") (pinfunction "NC_27") (pintype "bidirectional"))
    )
    (net (code "92") (name "unconnected-(U5-REFIN-Pad14)") (class "Default")
      (node (ref "U5") (pin "14") (pinfunction "REFIN_14") (pintype "input"))
    )
  )
)
